# Sheet1.net
KiCad netlist of a schematic drawn in Altium Designer
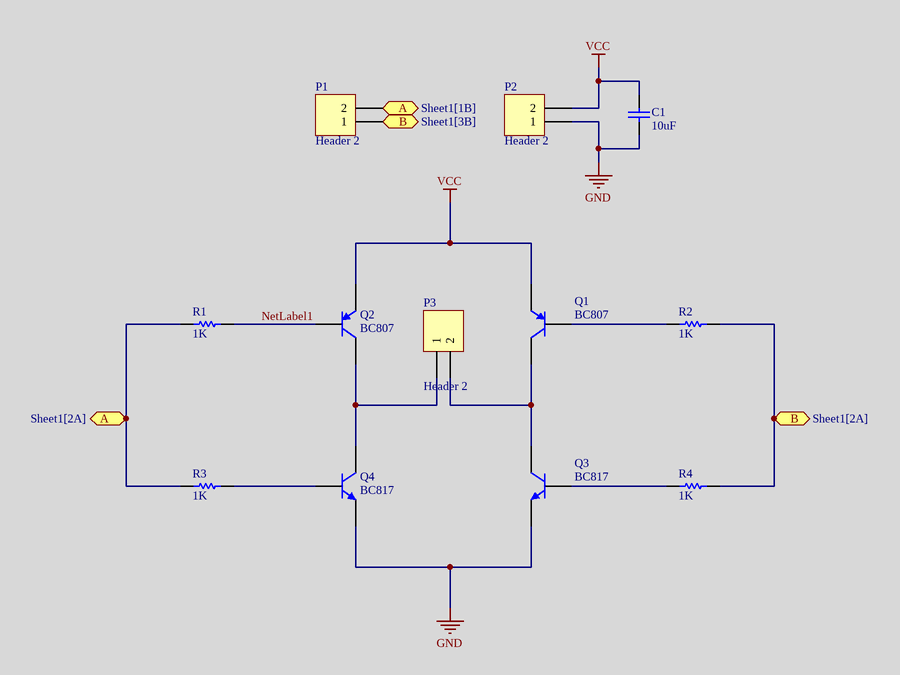
[diagram p0: Sheet1.SchDoc]

(export (version "E")
  (design (tool "Eeschema 10.0.6"))
  (components
    (comp (ref "C1")
      (value "10uF")
      (footprint "CAP1206")
      (description "TOTAL CAPACITOR SMD PACK")
      (fields (field (name "DESIGNER") "Abbas Basereh"))
      (libsource (lib "Altium") (part "CAP SMD PACKAGE"))
    )
    (comp (ref "P1")
      (value "Header 2")
      (footprint "HDR1X2")
      (description "Header, 2-Pin")
      (fields (field (name "PUBLISHER") "Altium Limited"))
      (libsource (lib "") (part "Header 2_1"))
    )
    (comp (ref "P2")
      (value "Header 2")
      (footprint "HDR1X2")
      (description "Header, 2-Pin")
      (fields (field (name "PUBLISHER") "Altium Limited"))
      (libsource (lib "") (part "Header 2_1"))
    )
    (comp (ref "P3")
      (value "Header 2")
      (footprint "HDR1X2")
      (description "Header, 2-Pin")
      (fields (field (name "PUBLISHER") "Altium Limited"))
      (libsource (lib "Altium") (part "Header 2"))
    )
    (comp (ref "Q1")
      (value "BC807")
      (footprint "SOT23_BEC_N")
      (description "PNP Bipolar Transistor")
      (fields (field (name "PUBLISHER") "Altium Limited"))
      (libsource (lib "Schematic") (part "PNP"))
    )
    (comp (ref "Q2")
      (value "BC807")
      (footprint "SOT23_BEC_N")
      (description "PNP Bipolar Transistor")
      (fields (field (name "PUBLISHER") "Altium Limited"))
      (libsource (lib "Schematic") (part "PNP"))
    )
    (comp (ref "Q3")
      (value "BC817")
      (footprint "SOT23_BEC_N")
      (description "NPN Bipolar Transistor")
      (fields (field (name "PUBLISHER") "Altium Limited"))
      (libsource (lib "Schematic") (part "NPN"))
    )
    (comp (ref "Q4")
      (value "BC817")
      (footprint "SOT23_BEC_N")
      (description "NPN Bipolar Transistor")
      (fields (field (name "PUBLISHER") "Altium Limited"))
      (libsource (lib "Schematic") (part "NPN"))
    )
    (comp (ref "R1")
      (value "1K")
      (footprint "RES1206")
      (description "TOTAL SMD RESISTOR PACK")
      (fields (field (name "DESIGNER") "Abbas Basereh"))
      (libsource (lib "Altium") (part "RES SMD PACKAGE"))
    )
    (comp (ref "R2")
      (value "1K")
      (footprint "RES1206")
      (description "TOTAL SMD RESISTOR PACK")
      (fields (field (name "DESIGNER") "Abbas Basereh"))
      (libsource (lib "Altium") (part "RES SMD PACKAGE"))
    )
    (comp (ref "R3")
      (value "1K")
      (footprint "RES1206")
      (description "TOTAL SMD RESISTOR PACK")
      (fields (field (name "DESIGNER") "Abbas Basereh"))
      (libsource (lib "Altium") (part "RES SMD PACKAGE"))
    )
    (comp (ref "R4")
      (value "1K")
      (footprint "RES1206")
      (description "TOTAL SMD RESISTOR PACK")
      (fields (field (name "DESIGNER") "Abbas Basereh"))
      (libsource (lib "Altium") (part "RES SMD PACKAGE"))
    )
  )
  (nets
    (net (code "1") (name "/A") (class "Default")
      (node (ref "P1") (pin "2") (pinfunction "2_2") (pintype "passive"))
      (node (ref "R1") (pin "1") (pinfunction "1_1") (pintype "passive"))
      (node (ref "R3") (pin "1") (pinfunction "1_1") (pintype "passive"))
    )
    (net (code "2") (name "/B") (class "Default")
      (node (ref "P1") (pin "1") (pinfunction "1_1") (pintype "passive"))
      (node (ref "R2") (pin "2") (pinfunction "2_2") (pintype "passive"))
      (node (ref "R4") (pin "2") (pinfunction "2_2") (pintype "passive"))
    )
    (net (code "3") (name "/NetLabel1") (class "Default")
      (node (ref "Q2") (pin "1") (pinfunction "B_1") (pintype "passive"))
      (node (ref "R1") (pin "2") (pinfunction "2_2") (pintype "passive"))
    )
    (net (code "4") (name "GND") (class "Default")
      (node (ref "C1") (pin "1") (pinfunction "1_1") (pintype "passive"))
      (node (ref "P2") (pin "1") (pinfunction "1_1") (pintype "passive"))
      (node (ref "Q3") (pin "2") (pinfunction "E_2") (pintype "passive"))
      (node (ref "Q4") (pin "2") (pinfunction "E_2") (pintype "passive"))
    )
    (net (code "5") (name "Net-(Q1-B)") (class "Default")
      (node (ref "Q1") (pin "1") (pinfunction "B_1") (pintype "passive"))
      (node (ref "R2") (pin "1") (pinfunction "1_1") (pintype "passive"))
    )
    (net (code "6") (name "Net-(Q1-C)") (class "Default")
      (node (ref "P3") (pin "2") (pinfunction "2_2") (pintype "passive"))
      (node (ref "Q1") (pin "3") (pinfunction "C_3") (pintype "passive"))
      (node (ref "Q3") (pin "3") (pinfunction "C_3") (pintype "passive"))
    )
    (net (code "7") (name "Net-(Q2-C)") (class "Default")
      (node (ref "P3") (pin "1") (pinfunction "1_1") (pintype "passive"))
      (node (ref "Q2") (pin "3") (pinfunction "C_3") (pintype "passive"))
      (node (ref "Q4") (pin "3") (pinfunction "C_3") (pintype "passive"))
    )
    (net (code "8") (name "Net-(Q3-B)") (class "Default")
      (node (ref "Q3") (pin "1") (pinfunction "B_1") (pintype "passive"))
      (node (ref "R4") (pin "1") (pinfunction "1_1") (pintype "passive"))
    )
    (net (code "9") (name "Net-(Q4-B)") (class "Default")
      (node (ref "Q4") (pin "1") (pinfunction "B_1") (pintype "passive"))
      (node (ref "R3") (pin "2") (pinfunction "2_2") (pintype "passive"))
    )
    (net (code "10") (name "VCC") (class "Default")
      (node (ref "C1") (pin "2") (pinfunction "2_2") (pintype "passive"))
      (node (ref "P2") (pin "2") (pinfunction "2_2") (pintype "passive"))
      (node (ref "Q1") (pin "2") (pinfunction "E_2") (pintype "passive"))
      (node (ref "Q2") (pin "2") (pinfunction "E_2") (pintype "passive"))
    )
  )
)
